# SDRAM.net
KiCad netlist of a schematic drawn in Altium Designer
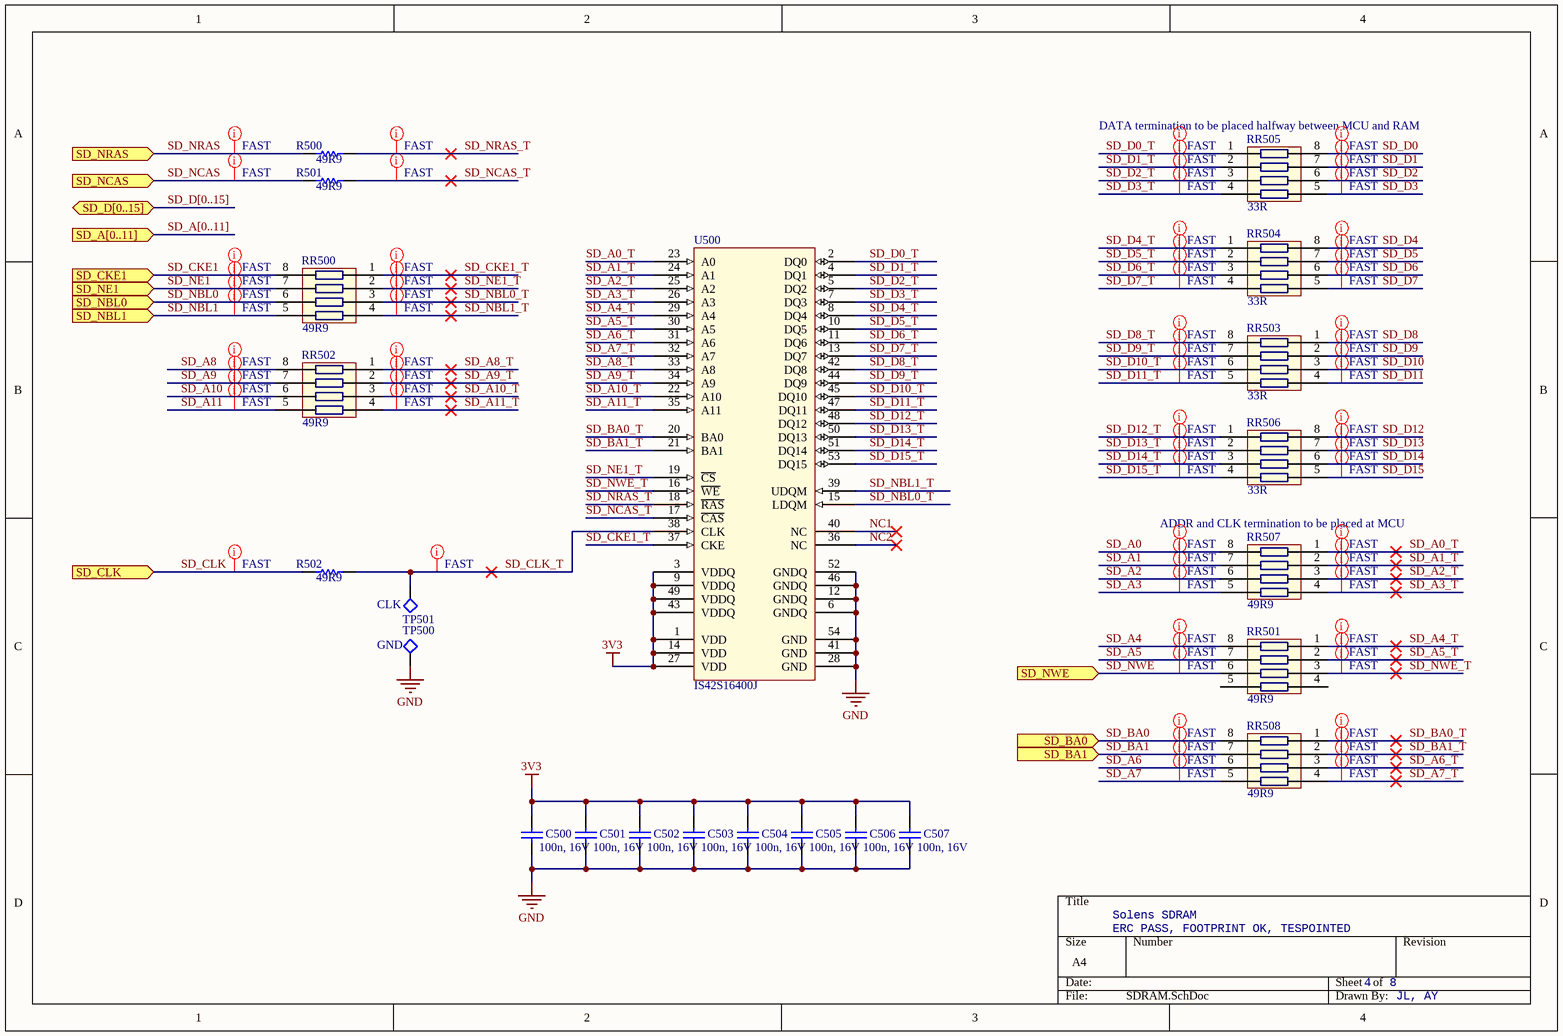
[diagram p0: SDRAM.SchDoc]

(export (version "E")
  (design (tool "Eeschema 10.0.6"))
  (components
    (comp (ref "C500")
      (value "100n, 16V")
      (footprint "CAP_0402")
      (description "Capacitor")
      (fields (field (name "Comment") "100n, 16V, 0402"))
      (libsource (lib "Miscellaneous Devices") (part "Cap"))
    )
    (comp (ref "C501")
      (value "100n, 16V")
      (footprint "CAP_0402")
      (description "Capacitor")
      (fields (field (name "Comment") "100n, 16V, 0402"))
      (libsource (lib "Miscellaneous Devices") (part "Cap"))
    )
    (comp (ref "C502")
      (value "100n, 16V")
      (footprint "CAP_0402")
      (description "Capacitor")
      (fields (field (name "Comment") "100n, 16V, 0402"))
      (libsource (lib "Miscellaneous Devices") (part "Cap"))
    )
    (comp (ref "C503")
      (value "100n, 16V")
      (footprint "CAP_0402")
      (description "Capacitor")
      (fields (field (name "Comment") "100n, 16V, 0402"))
      (libsource (lib "Miscellaneous Devices") (part "Cap"))
    )
    (comp (ref "C504")
      (value "100n, 16V")
      (footprint "CAP_0402")
      (description "Capacitor")
      (fields (field (name "Comment") "100n, 16V, 0402"))
      (libsource (lib "Miscellaneous Devices") (part "Cap"))
    )
    (comp (ref "C505")
      (value "100n, 16V")
      (footprint "CAP_0402")
      (description "Capacitor")
      (fields (field (name "Comment") "100n, 16V, 0402"))
      (libsource (lib "Miscellaneous Devices") (part "Cap"))
    )
    (comp (ref "C506")
      (value "100n, 16V")
      (footprint "CAP_0402")
      (description "Capacitor")
      (fields (field (name "Comment") "100n, 16V, 0402"))
      (libsource (lib "Miscellaneous Devices") (part "Cap"))
    )
    (comp (ref "C507")
      (value "100n, 16V")
      (footprint "CAP_0402")
      (description "Capacitor")
      (fields (field (name "Comment") "100n, 16V, 0402"))
      (libsource (lib "Miscellaneous Devices") (part "Cap"))
    )
    (comp (ref "R500")
      (value "49R9")
      (footprint "RES_0805")
      (description "Resistor")
      (fields (field (name "Comment") "49R9, 1/8W, 0805"))
      (libsource (lib "Miscellaneous Devices") (part "Res1"))
    )
    (comp (ref "R501")
      (value "49R9")
      (footprint "RES_0805")
      (description "Resistor")
      (fields (field (name "Comment") "49R9, 1/8W, 0805"))
      (libsource (lib "Miscellaneous Devices") (part "Res1"))
    )
    (comp (ref "R502")
      (value "49R9")
      (footprint "RES_0805")
      (description "Resistor")
      (fields (field (name "Comment") "49R9, 1/8W, 0805"))
      (libsource (lib "Miscellaneous Devices") (part "Res1"))
    )
    (comp (ref "RR500")
      (value "49R9")
      (footprint "CAC-80P319X150-8M")
      (description "4 element resistor array")
      (fields (field (name "Comment") "CRA6S849.9ACT-ND"))
      (libsource (lib "Schlib1") (part "RES_ARR_4"))
    )
    (comp (ref "RR501")
      (value "49R9")
      (footprint "CAC-80P319X150-8M")
      (description "4 element resistor array")
      (fields (field (name "Comment") "CRA6S849.9ACT-ND"))
      (libsource (lib "Schlib1") (part "RES_ARR_4"))
    )
    (comp (ref "RR502")
      (value "49R9")
      (footprint "CAC-80P319X150-8M")
      (description "4 element resistor array")
      (fields (field (name "Comment") "CRA6S849.9ACT-ND"))
      (libsource (lib "Schlib1") (part "RES_ARR_4"))
    )
    (comp (ref "RR503")
      (value "33R")
      (footprint "CAC-80P319X150-8M")
      (description "4 element resistor array")
      (fields (field (name "Comment") "CRA6S833CT-ND"))
      (libsource (lib "Schlib1") (part "RES_ARR_4"))
    )
    (comp (ref "RR504")
      (value "33R")
      (footprint "CAC-80P319X150-8M")
      (description "4 element resistor array")
      (fields (field (name "Comment") "CRA6S833CT-ND"))
      (libsource (lib "") (part "RES_ARR_4_1"))
    )
    (comp (ref "RR505")
      (value "33R")
      (footprint "CAC-80P319X150-8M")
      (description "4 element resistor array")
      (fields (field (name "Comment") "CRA6S833CT-ND"))
      (libsource (lib "") (part "RES_ARR_4_1"))
    )
    (comp (ref "RR506")
      (value "33R")
      (footprint "CAC-80P319X150-8M")
      (description "4 element resistor array")
      (fields (field (name "Comment") "CRA6S833CT-ND"))
      (libsource (lib "") (part "RES_ARR_4_1"))
    )
    (comp (ref "RR507")
      (value "49R9")
      (footprint "CAC-80P319X150-8M")
      (description "4 element resistor array")
      (fields (field (name "Comment") "CRA6S849.9ACT-ND"))
      (libsource (lib "Schlib1") (part "RES_ARR_4"))
    )
    (comp (ref "RR508")
      (value "49R9")
      (footprint "CAC-80P319X150-8M")
      (description "4 element resistor array")
      (fields (field (name "Comment") "CRA6S849.9ACT-ND"))
      (libsource (lib "Schlib1") (part "RES_ARR_4"))
    )
    (comp (ref "TP500")
      (value "TP (DNP)")
      (footprint "TP_TINY")
      (fields (field (name "VISIBLENETNAME") "GND"))
      (libsource (lib "Schlib1") (part "TP_TINY"))
    )
    (comp (ref "TP501")
      (value "TP (DNP)")
      (footprint "TP_TINY")
      (fields (field (name "VISIBLENETNAME") "CLK"))
      (libsource (lib "Schlib1") (part "TP_TINY"))
    )
    (comp (ref "U500")
      (value "IS42S16400J, TSOP-54")
      (footprint "TSOP80P1170X120-54N")
      (description "1Mb x 16 x 4 bank (64 Mbit) SDRAM")
      (fields (field (name "PARTNUMBER") "IS42S16400J"))
      (libsource (lib "Schlib1") (part "IS42S16400J"))
    )
  )
  (nets
    (net (code "1") (name "/NC1") (class "Default")
      (node (ref "U500") (pin "40") (pinfunction "NC_40") (pintype "passive+no_connect"))
    )
    (net (code "2") (name "/NC2") (class "Default")
      (node (ref "U500") (pin "36") (pinfunction "NC_36") (pintype "passive+no_connect"))
    )
    (net (code "3") (name "/SD_A0") (class "Default")
      (node (ref "RR507") (pin "8") (pinfunction "1B_8") (pintype "passive"))
    )
    (net (code "4") (name "/SD_A0_T") (class "Default")
      (node (ref "RR507") (pin "1") (pinfunction "1A_1") (pintype "passive"))
      (node (ref "U500") (pin "23") (pinfunction "A0_23") (pintype "input"))
    )
    (net (code "5") (name "/SD_A1") (class "Default")
      (node (ref "RR507") (pin "7") (pinfunction "2B_7") (pintype "passive"))
    )
    (net (code "6") (name "/SD_A1_T") (class "Default")
      (node (ref "RR507") (pin "2") (pinfunction "2A_2") (pintype "passive"))
      (node (ref "U500") (pin "24") (pinfunction "A1_24") (pintype "input"))
    )
    (net (code "7") (name "/SD_A2") (class "Default")
      (node (ref "RR507") (pin "6") (pinfunction "3B_6") (pintype "passive"))
    )
    (net (code "8") (name "/SD_A2_T") (class "Default")
      (node (ref "RR507") (pin "3") (pinfunction "3A_3") (pintype "passive"))
      (node (ref "U500") (pin "25") (pinfunction "A2_25") (pintype "input"))
    )
    (net (code "9") (name "/SD_A3") (class "Default")
      (node (ref "RR507") (pin "5") (pinfunction "4B_5") (pintype "passive"))
    )
    (net (code "10") (name "/SD_A3_T") (class "Default")
      (node (ref "RR507") (pin "4") (pinfunction "4A_4") (pintype "passive"))
      (node (ref "U500") (pin "26") (pinfunction "A3_26") (pintype "input"))
    )
    (net (code "11") (name "/SD_A4") (class "Default")
      (node (ref "RR501") (pin "8") (pinfunction "1B_8") (pintype "passive"))
    )
    (net (code "12") (name "/SD_A4_T") (class "Default")
      (node (ref "RR501") (pin "1") (pinfunction "1A_1") (pintype "passive"))
      (node (ref "U500") (pin "29") (pinfunction "A4_29") (pintype "input"))
    )
    (net (code "13") (name "/SD_A5") (class "Default")
      (node (ref "RR501") (pin "7") (pinfunction "2B_7") (pintype "passive"))
    )
    (net (code "14") (name "/SD_A5_T") (class "Default")
      (node (ref "RR501") (pin "2") (pinfunction "2A_2") (pintype "passive"))
      (node (ref "U500") (pin "30") (pinfunction "A5_30") (pintype "input"))
    )
    (net (code "15") (name "/SD_A6") (class "Default")
      (node (ref "RR508") (pin "6") (pinfunction "3B_6") (pintype "passive"))
    )
    (net (code "16") (name "/SD_A6_T") (class "Default")
      (node (ref "RR508") (pin "3") (pinfunction "3A_3") (pintype "passive"))
      (node (ref "U500") (pin "31") (pinfunction "A6_31") (pintype "input"))
    )
    (net (code "17") (name "/SD_A7") (class "Default")
      (node (ref "RR508") (pin "5") (pinfunction "4B_5") (pintype "passive"))
    )
    (net (code "18") (name "/SD_A7_T") (class "Default")
      (node (ref "RR508") (pin "4") (pinfunction "4A_4") (pintype "passive"))
      (node (ref "U500") (pin "32") (pinfunction "A7_32") (pintype "input"))
    )
    (net (code "19") (name "/SD_A8") (class "Default")
      (node (ref "RR502") (pin "8") (pinfunction "1B_8") (pintype "passive"))
    )
    (net (code "20") (name "/SD_A8_T") (class "Default")
      (node (ref "RR502") (pin "1") (pinfunction "1A_1") (pintype "passive"))
      (node (ref "U500") (pin "33") (pinfunction "A8_33") (pintype "input"))
    )
    (net (code "21") (name "/SD_A9") (class "Default")
      (node (ref "RR502") (pin "7") (pinfunction "2B_7") (pintype "passive"))
    )
    (net (code "22") (name "/SD_A9_T") (class "Default")
      (node (ref "RR502") (pin "2") (pinfunction "2A_2") (pintype "passive"))
      (node (ref "U500") (pin "34") (pinfunction "A9_34") (pintype "input"))
    )
    (net (code "23") (name "/SD_A10") (class "Default")
      (node (ref "RR502") (pin "6") (pinfunction "3B_6") (pintype "passive"))
    )
    (net (code "24") (name "/SD_A10_T") (class "Default")
      (node (ref "RR502") (pin "3") (pinfunction "3A_3") (pintype "passive"))
      (node (ref "U500") (pin "22") (pinfunction "A10_22") (pintype "input"))
    )
    (net (code "25") (name "/SD_A11") (class "Default")
      (node (ref "RR502") (pin "5") (pinfunction "4B_5") (pintype "passive"))
    )
    (net (code "26") (name "/SD_A11_T") (class "Default")
      (node (ref "RR502") (pin "4") (pinfunction "4A_4") (pintype "passive"))
      (node (ref "U500") (pin "35") (pinfunction "A11_35") (pintype "input"))
    )
    (net (code "28") (name "/SD_BA0") (class "Default")
      (node (ref "RR508") (pin "8") (pinfunction "1B_8") (pintype "passive"))
    )
    (net (code "29") (name "/SD_BA0_T") (class "Default")
      (node (ref "RR508") (pin "1") (pinfunction "1A_1") (pintype "passive"))
      (node (ref "U500") (pin "20") (pinfunction "BA0_20") (pintype "input"))
    )
    (net (code "30") (name "/SD_BA1") (class "Default")
      (node (ref "RR508") (pin "7") (pinfunction "2B_7") (pintype "passive"))
    )
    (net (code "31") (name "/SD_BA1_T") (class "Default")
      (node (ref "RR508") (pin "2") (pinfunction "2A_2") (pintype "passive"))
      (node (ref "U500") (pin "21") (pinfunction "BA1_21") (pintype "input"))
    )
    (net (code "32") (name "/SD_CKE1") (class "Default")
      (node (ref "RR500") (pin "8") (pinfunction "1B_8") (pintype "passive"))
    )
    (net (code "33") (name "/SD_CKE1_T") (class "Default")
      (node (ref "RR500") (pin "1") (pinfunction "1A_1") (pintype "passive"))
      (node (ref "U500") (pin "37") (pinfunction "CKE_37") (pintype "input"))
    )
    (net (code "34") (name "/SD_CLK") (class "Default")
      (node (ref "R502") (pin "1") (pinfunction "1_1") (pintype "passive"))
    )
    (net (code "35") (name "/SD_CLK_T") (class "Default")
      (node (ref "R502") (pin "2") (pinfunction "2_2") (pintype "passive"))
      (node (ref "TP501") (pin "1") (pinfunction "1_1") (pintype "passive"))
      (node (ref "U500") (pin "38") (pinfunction "CLK_38") (pintype "input"))
    )
    (net (code "36") (name "/SD_D0") (class "Default")
      (node (ref "RR505") (pin "8") (pinfunction "1B_8") (pintype "passive"))
    )
    (net (code "37") (name "/SD_D0_T") (class "Default")
      (node (ref "RR505") (pin "1") (pinfunction "1A_1") (pintype "passive"))
      (node (ref "U500") (pin "2") (pinfunction "DQ0_2") (pintype "bidirectional"))
    )
    (net (code "38") (name "/SD_D1") (class "Default")
      (node (ref "RR505") (pin "7") (pinfunction "2B_7") (pintype "passive"))
    )
    (net (code "39") (name "/SD_D1_T") (class "Default")
      (node (ref "RR505") (pin "2") (pinfunction "2A_2") (pintype "passive"))
      (node (ref "U500") (pin "4") (pinfunction "DQ1_4") (pintype "bidirectional"))
    )
    (net (code "40") (name "/SD_D2") (class "Default")
      (node (ref "RR505") (pin "6") (pinfunction "3B_6") (pintype "passive"))
    )
    (net (code "41") (name "/SD_D2_T") (class "Default")
      (node (ref "RR505") (pin "3") (pinfunction "3A_3") (pintype "passive"))
      (node (ref "U500") (pin "5") (pinfunction "DQ2_5") (pintype "bidirectional"))
    )
    (net (code "42") (name "/SD_D3") (class "Default")
      (node (ref "RR505") (pin "5") (pinfunction "4B_5") (pintype "passive"))
    )
    (net (code "43") (name "/SD_D3_T") (class "Default")
      (node (ref "RR505") (pin "4") (pinfunction "4A_4") (pintype "passive"))
      (node (ref "U500") (pin "7") (pinfunction "DQ3_7") (pintype "bidirectional"))
    )
    (net (code "44") (name "/SD_D4") (class "Default")
      (node (ref "RR504") (pin "8") (pinfunction "1B_8") (pintype "passive"))
    )
    (net (code "45") (name "/SD_D4_T") (class "Default")
      (node (ref "RR504") (pin "1") (pinfunction "1A_1") (pintype "passive"))
      (node (ref "U500") (pin "8") (pinfunction "DQ4_8") (pintype "bidirectional"))
    )
    (net (code "46") (name "/SD_D5") (class "Default")
      (node (ref "RR504") (pin "7") (pinfunction "2B_7") (pintype "passive"))
    )
    (net (code "47") (name "/SD_D5_T") (class "Default")
      (node (ref "RR504") (pin "2") (pinfunction "2A_2") (pintype "passive"))
      (node (ref "U500") (pin "10") (pinfunction "DQ5_10") (pintype "bidirectional"))
    )
    (net (code "48") (name "/SD_D6") (class "Default")
      (node (ref "RR504") (pin "6") (pinfunction "3B_6") (pintype "passive"))
    )
    (net (code "49") (name "/SD_D6_T") (class "Default")
      (node (ref "RR504") (pin "3") (pinfunction "3A_3") (pintype "passive"))
      (node (ref "U500") (pin "11") (pinfunction "DQ6_11") (pintype "bidirectional"))
    )
    (net (code "50") (name "/SD_D7") (class "Default")
      (node (ref "RR504") (pin "5") (pinfunction "4B_5") (pintype "passive"))
    )
    (net (code "51") (name "/SD_D7_T") (class "Default")
      (node (ref "RR504") (pin "4") (pinfunction "4A_4") (pintype "passive"))
      (node (ref "U500") (pin "13") (pinfunction "DQ7_13") (pintype "bidirectional"))
    )
    (net (code "52") (name "/SD_D8") (class "Default")
      (node (ref "RR503") (pin "1") (pinfunction "1A_1") (pintype "passive"))
    )
    (net (code "53") (name "/SD_D8_T") (class "Default")
      (node (ref "RR503") (pin "8") (pinfunction "1B_8") (pintype "passive"))
      (node (ref "U500") (pin "42") (pinfunction "DQ8_42") (pintype "bidirectional"))
    )
    (net (code "54") (name "/SD_D9") (class "Default")
      (node (ref "RR503") (pin "2") (pinfunction "2A_2") (pintype "passive"))
    )
    (net (code "55") (name "/SD_D9_T") (class "Default")
      (node (ref "RR503") (pin "7") (pinfunction "2B_7") (pintype "passive"))
      (node (ref "U500") (pin "44") (pinfunction "DQ9_44") (pintype "bidirectional"))
    )
    (net (code "56") (name "/SD_D10") (class "Default")
      (node (ref "RR503") (pin "3") (pinfunction "3A_3") (pintype "passive"))
    )
    (net (code "57") (name "/SD_D10_T") (class "Default")
      (node (ref "RR503") (pin "6") (pinfunction "3B_6") (pintype "passive"))
      (node (ref "U500") (pin "45") (pinfunction "DQ10_45") (pintype "bidirectional"))
    )
    (net (code "58") (name "/SD_D11") (class "Default")
      (node (ref "RR503") (pin "4") (pinfunction "4A_4") (pintype "passive"))
    )
    (net (code "59") (name "/SD_D11_T") (class "Default")
      (node (ref "RR503") (pin "5") (pinfunction "4B_5") (pintype "passive"))
      (node (ref "U500") (pin "47") (pinfunction "DQ11_47") (pintype "bidirectional"))
    )
    (net (code "60") (name "/SD_D12") (class "Default")
      (node (ref "RR506") (pin "8") (pinfunction "1B_8") (pintype "passive"))
    )
    (net (code "61") (name "/SD_D12_T") (class "Default")
      (node (ref "RR506") (pin "1") (pinfunction "1A_1") (pintype "passive"))
      (node (ref "U500") (pin "48") (pinfunction "DQ12_48") (pintype "bidirectional"))
    )
    (net (code "62") (name "/SD_D13") (class "Default")
      (node (ref "RR506") (pin "7") (pinfunction "2B_7") (pintype "passive"))
    )
    (net (code "63") (name "/SD_D13_T") (class "Default")
      (node (ref "RR506") (pin "2") (pinfunction "2A_2") (pintype "passive"))
      (node (ref "U500") (pin "50") (pinfunction "DQ13_50") (pintype "bidirectional"))
    )
    (net (code "64") (name "/SD_D14") (class "Default")
      (node (ref "RR506") (pin "6") (pinfunction "3B_6") (pintype "passive"))
    )
    (net (code "65") (name "/SD_D14_T") (class "Default")
      (node (ref "RR506") (pin "3") (pinfunction "3A_3") (pintype "passive"))
      (node (ref "U500") (pin "51") (pinfunction "DQ14_51") (pintype "bidirectional"))
    )
    (net (code "66") (name "/SD_D15") (class "Default")
      (node (ref "RR506") (pin "5") (pinfunction "4B_5") (pintype "passive"))
    )
    (net (code "67") (name "/SD_D15_T") (class "Default")
      (node (ref "RR506") (pin "4") (pinfunction "4A_4") (pintype "passive"))
      (node (ref "U500") (pin "53") (pinfunction "DQ15_53") (pintype "bidirectional"))
    )
    (net (code "69") (name "/SD_NBL0") (class "Default")
      (node (ref "RR500") (pin "6") (pinfunction "3B_6") (pintype "passive"))
    )
    (net (code "70") (name "/SD_NBL0_T") (class "Default")
      (node (ref "RR500") (pin "3") (pinfunction "3A_3") (pintype "passive"))
      (node (ref "U500") (pin "15") (pinfunction "LDQM_15") (pintype "input"))
    )
    (net (code "71") (name "/SD_NBL1") (class "Default")
      (node (ref "RR500") (pin "5") (pinfunction "4B_5") (pintype "passive"))
    )
    (net (code "72") (name "/SD_NBL1_T") (class "Default")
      (node (ref "RR500") (pin "4") (pinfunction "4A_4") (pintype "passive"))
      (node (ref "U500") (pin "39") (pinfunction "UDQM_39") (pintype "input"))
    )
    (net (code "73") (name "/SD_NCAS") (class "Default")
      (node (ref "R501") (pin "1") (pinfunction "1_1") (pintype "passive"))
    )
    (net (code "74") (name "/SD_NCAS_T") (class "Default")
      (node (ref "R501") (pin "2") (pinfunction "2_2") (pintype "passive"))
      (node (ref "U500") (pin "17") (pinfunction "~{CAS}_17") (pintype "input"))
    )
    (net (code "75") (name "/SD_NE1") (class "Default")
      (node (ref "RR500") (pin "7") (pinfunction "2B_7") (pintype "passive"))
    )
    (net (code "76") (name "/SD_NE1_T") (class "Default")
      (node (ref "RR500") (pin "2") (pinfunction "2A_2") (pintype "passive"))
      (node (ref "U500") (pin "19") (pinfunction "~{CS}_19") (pintype "input"))
    )
    (net (code "77") (name "/SD_NRAS") (class "Default")
      (node (ref "R500") (pin "1") (pinfunction "1_1") (pintype "passive"))
    )
    (net (code "78") (name "/SD_NRAS_T") (class "Default")
      (node (ref "R500") (pin "2") (pinfunction "2_2") (pintype "passive"))
      (node (ref "U500") (pin "18") (pinfunction "~{RAS}_18") (pintype "input"))
    )
    (net (code "79") (name "/SD_NWE") (class "Default")
      (node (ref "RR501") (pin "6") (pinfunction "3B_6") (pintype "passive"))
    )
    (net (code "80") (name "/SD_NWE_T") (class "Default")
      (node (ref "RR501") (pin "3") (pinfunction "3A_3") (pintype "passive"))
      (node (ref "U500") (pin "16") (pinfunction "~{WE}_16") (pintype "input"))
    )
    (net (code "81") (name "3V3") (class "Default")
      (node (ref "C500") (pin "1") (pinfunction "1_1") (pintype "passive"))
      (node (ref "C501") (pin "1") (pinfunction "1_1") (pintype "passive"))
      (node (ref "C502") (pin "1") (pinfunction "1_1") (pintype "passive"))
      (node (ref "C503") (pin "1") (pinfunction "1_1") (pintype "passive"))
      (node (ref "C504") (pin "1") (pinfunction "1_1") (pintype "passive"))
      (node (ref "C505") (pin "1") (pinfunction "1_1") (pintype "passive"))
      (node (ref "C506") (pin "1") (pinfunction "1_1") (pintype "passive"))
      (node (ref "C507") (pin "1") (pinfunction "1_1") (pintype "passive"))
      (node (ref "U500") (pin "1") (pinfunction "VDD_1") (pintype "power_in"))
      (node (ref "U500") (pin "14") (pinfunction "VDD_14") (pintype "power_in"))
      (node (ref "U500") (pin "27") (pinfunction "VDD_27") (pintype "power_in"))
      (node (ref "U500") (pin "3") (pinfunction "VDDQ_3") (pintype "power_in"))
      (node (ref "U500") (pin "43") (pinfunction "VDDQ_43") (pintype "power_in"))
      (node (ref "U500") (pin "49") (pinfunction "VDDQ_49") (pintype "power_in"))
      (node (ref "U500") (pin "9") (pinfunction "VDDQ_9") (pintype "power_in"))
    )
    (net (code "82") (name "GND") (class "Default")
      (node (ref "C500") (pin "2") (pinfunction "2_2") (pintype "passive"))
      (node (ref "C501") (pin "2") (pinfunction "2_2") (pintype "passive"))
      (node (ref "C502") (pin "2") (pinfunction "2_2") (pintype "passive"))
      (node (ref "C503") (pin "2") (pinfunction "2_2") (pintype "passive"))
      (node (ref "C504") (pin "2") (pinfunction "2_2") (pintype "passive"))
      (node (ref "C505") (pin "2") (pinfunction "2_2") (pintype "passive"))
      (node (ref "C506") (pin "2") (pinfunction "2_2") (pintype "passive"))
      (node (ref "C507") (pin "2") (pinfunction "2_2") (pintype "passive"))
      (node (ref "TP500") (pin "1") (pinfunction "1_1") (pintype "passive"))
      (node (ref "U500") (pin "12") (pinfunction "GNDQ_12") (pintype "power_in"))
      (node (ref "U500") (pin "28") (pinfunction "GND_28") (pintype "power_in"))
      (node (ref "U500") (pin "41") (pinfunction "GND_41") (pintype "power_in"))
      (node (ref "U500") (pin "46") (pinfunction "GNDQ_46") (pintype "power_in"))
      (node (ref "U500") (pin "52") (pinfunction "GNDQ_52") (pintype "power_in"))
      (node (ref "U500") (pin "54") (pinfunction "GND_54") (pintype "power_in"))
      (node (ref "U500") (pin "6") (pinfunction "GNDQ_6") (pintype "power_in"))
    )
    (net (code "83") (name "unconnected-(RR501-4A-Pad4)") (class "Default")
      (node (ref "RR501") (pin "4") (pinfunction "4A_4") (pintype "passive"))
    )
    (net (code "84") (name "unconnected-(RR501-4B-Pad5)") (class "Default")
      (node (ref "RR501") (pin "5") (pinfunction "4B_5") (pintype "passive"))
    )
  )
)
